# LEDdriver-LM3409.net
KiCad netlist of a schematic drawn in Altium Designer
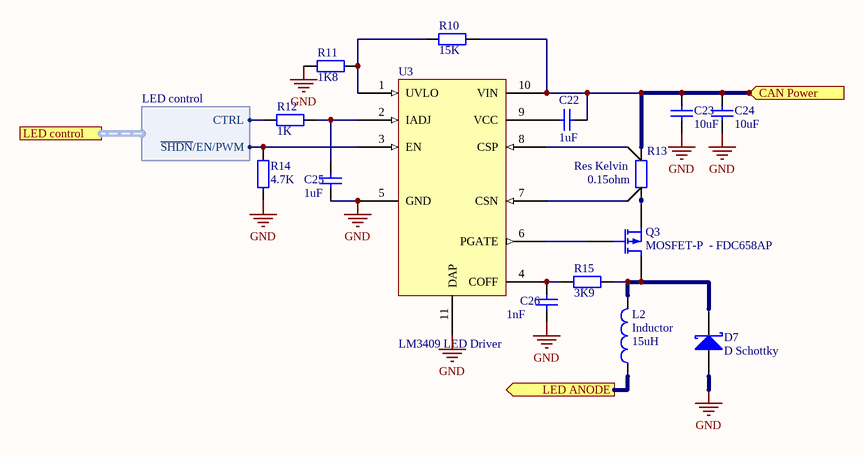
[diagram p0: LEDdriver-LM3409.SchDoc]

(export (version "E")
  (design (tool "Eeschema 10.0.6"))
  (components
    (comp (ref "C22")
      (value "1uF")
      (footprint "C0603")
      (description "Capacitor")
      (fields (field (name "Comment") "Cap") (field (name "PUBLISHER") "Altium Limited"))
      (libsource (lib "Miscellaneous Devices") (part "Cap"))
    )
    (comp (ref "C23")
      (value "10uF")
      (footprint "Capacitor 1210 (3225) package")
      (description "Capacitor")
      (fields (field (name "Comment") "Cap") (field (name "PUBLISHER") "Altium Limited"))
      (libsource (lib "Miscellaneous Devices") (part "Cap"))
    )
    (comp (ref "C24")
      (value "10uF")
      (footprint "Capacitor 1210 (3225) package")
      (description "Capacitor")
      (fields (field (name "Comment") "Cap") (field (name "PUBLISHER") "Altium Limited"))
      (libsource (lib "Miscellaneous Devices") (part "Cap"))
    )
    (comp (ref "C25")
      (value "1uF")
      (footprint "C0603")
      (description "Capacitor")
      (fields (field (name "Comment") "Cap") (field (name "PUBLISHER") "Altium Limited"))
      (libsource (lib "Miscellaneous Devices") (part "Cap"))
    )
    (comp (ref "C26")
      (value "1nF")
      (footprint "C0603")
      (description "Capacitor")
      (fields (field (name "Comment") "Cap") (field (name "PUBLISHER") "Altium Limited"))
      (libsource (lib "Miscellaneous Devices") (part "Cap"))
    )
    (comp (ref "D7")
      (value "D Schottky")
      (footprint "Schottky rectifier")
      (description "Schottky Diode")
      (fields (field (name "PUBLISHER") "Altium Limited"))
      (libsource (lib "Miscellaneous Devices") (part "D Schottky"))
    )
    (comp (ref "L2")
      (value "Inductor")
      (footprint "Inductor 3131")
      (fields (field (name "ALTIUM_VALUE") "15uH") (field (name "PUBLISHER") "Altium Limited"))
      (libsource (lib "Miscellaneous Devices") (part "Inductor"))
    )
    (comp (ref "Q3")
      (value "MOSFET-P  - FDC658AP")
      (footprint "SuperSOT6 - FDC658AP")
      (description "P-Channel MOSFET")
      (fields (field (name "PUBLISHER") "Altium Limited"))
      (libsource (lib "Miscellaneous Devices") (part "MOSFET-P"))
    )
    (comp (ref "R10")
      (value "15K")
      (footprint "R0603")
      (description "Resistor")
      (fields (field (name "Comment") "Res"))
      (libsource (lib "") (part "Res2_1"))
    )
    (comp (ref "R11")
      (value "1K8")
      (footprint "R0603")
      (description "Resistor")
      (fields (field (name "Comment") "Res"))
      (libsource (lib "") (part "Res2_1"))
    )
    (comp (ref "R12")
      (value "1K")
      (footprint "R0603")
      (description "Resistor")
      (fields (field (name "Comment") "Res"))
      (libsource (lib "") (part "Res2_1"))
    )
    (comp (ref "R13")
      (value "Res Kelvin")
      (footprint "2512 package + Kelvin Cons - ERJ1TR Rsns")
      (description "Resistor Kelvin")
      (fields (field (name "ALTIUM_VALUE") "0.15ohm") (field (name "PUBLISHER") "Altium Limited"))
      (libsource (lib "resistor-kelvin") (part "Res Kelvin"))
    )
    (comp (ref "R14")
      (value "4.7K")
      (footprint "R0603")
      (description "Resistor")
      (fields (field (name "Comment") "Res"))
      (libsource (lib "Miscellaneous Devices") (part "Res2"))
    )
    (comp (ref "R15")
      (value "3K9")
      (footprint "R0603")
      (description "Resistor")
      (fields (field (name "Comment") "Res"))
      (libsource (lib "") (part "Res2_1"))
    )
    (comp (ref "U3")
      (value "LM3409 LED Driver")
      (footprint "10eMSOP + thermal pad - LM3409")
      (description "PFET Buck Controller for High Power LED Drivers")
      (libsource (lib "LM3409") (part "LM3409"))
    )
  )
  (nets
    (net (code "3") (name "/CAN Power") (class "Default")
      (node (ref "C22") (pin "1") (pinfunction "1_1") (pintype "passive"))
      (node (ref "C23") (pin "1") (pinfunction "1_1") (pintype "passive"))
      (node (ref "C24") (pin "1") (pinfunction "1_1") (pintype "passive"))
      (node (ref "R10") (pin "1") (pinfunction "1_1") (pintype "passive"))
      (node (ref "R13") (pin "2") (pinfunction "2_2") (pintype "passive"))
      (node (ref "U3") (pin "10") (pinfunction "VIN_10") (pintype "passive"))
    )
    (net (code "4") (name "/CTRL") (class "Default")
      (node (ref "R12") (pin "2") (pinfunction "2_2") (pintype "passive"))
    )
    (net (code "5") (name "/LED ANODE") (class "Default")
      (node (ref "L2") (pin "1") (pinfunction "1_1") (pintype "passive"))
    )
    (net (code "7") (name "/~{SHDN}{slash}EN{slash}PWM") (class "Default")
      (node (ref "R14") (pin "2") (pinfunction "2_2") (pintype "passive"))
      (node (ref "U3") (pin "3") (pinfunction "EN_3") (pintype "input"))
    )
    (net (code "8") (name "GND") (class "Default")
      (node (ref "C23") (pin "2") (pinfunction "2_2") (pintype "passive"))
      (node (ref "C24") (pin "2") (pinfunction "2_2") (pintype "passive"))
      (node (ref "C25") (pin "2") (pinfunction "2_2") (pintype "passive"))
      (node (ref "C26") (pin "2") (pinfunction "2_2") (pintype "passive"))
      (node (ref "D7") (pin "1") (pinfunction "A_1") (pintype "passive"))
      (node (ref "R11") (pin "2") (pinfunction "2_2") (pintype "passive"))
      (node (ref "R14") (pin "1") (pinfunction "1_1") (pintype "passive"))
      (node (ref "U3") (pin "11") (pinfunction "DAP_11") (pintype "power_in"))
      (node (ref "U3") (pin "5") (pinfunction "GND_5") (pintype "power_in"))
    )
    (net (code "9") (name "Net-(D7-K)") (class "Default")
      (node (ref "D7") (pin "2") (pinfunction "K_2") (pintype "passive"))
      (node (ref "L2") (pin "2") (pinfunction "2_2") (pintype "passive"))
      (node (ref "Q3") (pin "1") (pinfunction "D_1") (pintype "passive"))
      (node (ref "R15") (pin "1") (pinfunction "1_1") (pintype "passive"))
    )
    (net (code "10") (name "Net-(Q3-G)") (class "Default")
      (node (ref "Q3") (pin "2") (pinfunction "G_2") (pintype "passive"))
      (node (ref "U3") (pin "6") (pinfunction "PGATE_6") (pintype "output"))
    )
    (net (code "11") (name "Net-(Q3-S)") (class "Default")
      (node (ref "Q3") (pin "3") (pinfunction "S_3") (pintype "passive"))
      (node (ref "R13") (pin "1") (pinfunction "1_1") (pintype "passive"))
    )
    (net (code "12") (name "Net-(U3-COFF)") (class "Default")
      (node (ref "C26") (pin "1") (pinfunction "1_1") (pintype "passive"))
      (node (ref "R15") (pin "2") (pinfunction "2_2") (pintype "passive"))
      (node (ref "U3") (pin "4") (pinfunction "COFF_4") (pintype "passive"))
    )
    (net (code "13") (name "Net-(U3-CSN)") (class "Default")
      (node (ref "R13") (pin "3") (pinfunction "3_3") (pintype "power_in"))
      (node (ref "U3") (pin "7") (pinfunction "CSN_7") (pintype "input"))
    )
    (net (code "14") (name "Net-(U3-CSP)") (class "Default")
      (node (ref "R13") (pin "4") (pinfunction "4_4") (pintype "power_in"))
      (node (ref "U3") (pin "8") (pinfunction "CSP_8") (pintype "input"))
    )
    (net (code "15") (name "Net-(U3-IADJ)") (class "Default")
      (node (ref "C25") (pin "1") (pinfunction "1_1") (pintype "passive"))
      (node (ref "R12") (pin "1") (pinfunction "1_1") (pintype "passive"))
      (node (ref "U3") (pin "2") (pinfunction "IADJ_2") (pintype "input"))
    )
    (net (code "16") (name "Net-(U3-UVLO)") (class "Default")
      (node (ref "R10") (pin "2") (pinfunction "2_2") (pintype "passive"))
      (node (ref "R11") (pin "1") (pinfunction "1_1") (pintype "passive"))
      (node (ref "U3") (pin "1") (pinfunction "UVLO_1") (pintype "input"))
    )
    (net (code "17") (name "Net-(U3-VCC)") (class "Default")
      (node (ref "C22") (pin "2") (pinfunction "2_2") (pintype "passive"))
      (node (ref "U3") (pin "9") (pinfunction "VCC_9") (pintype "power_in"))
    )
  )
)
